# exp31ac.net
KiCad netlist of a schematic drawn in EAGLE
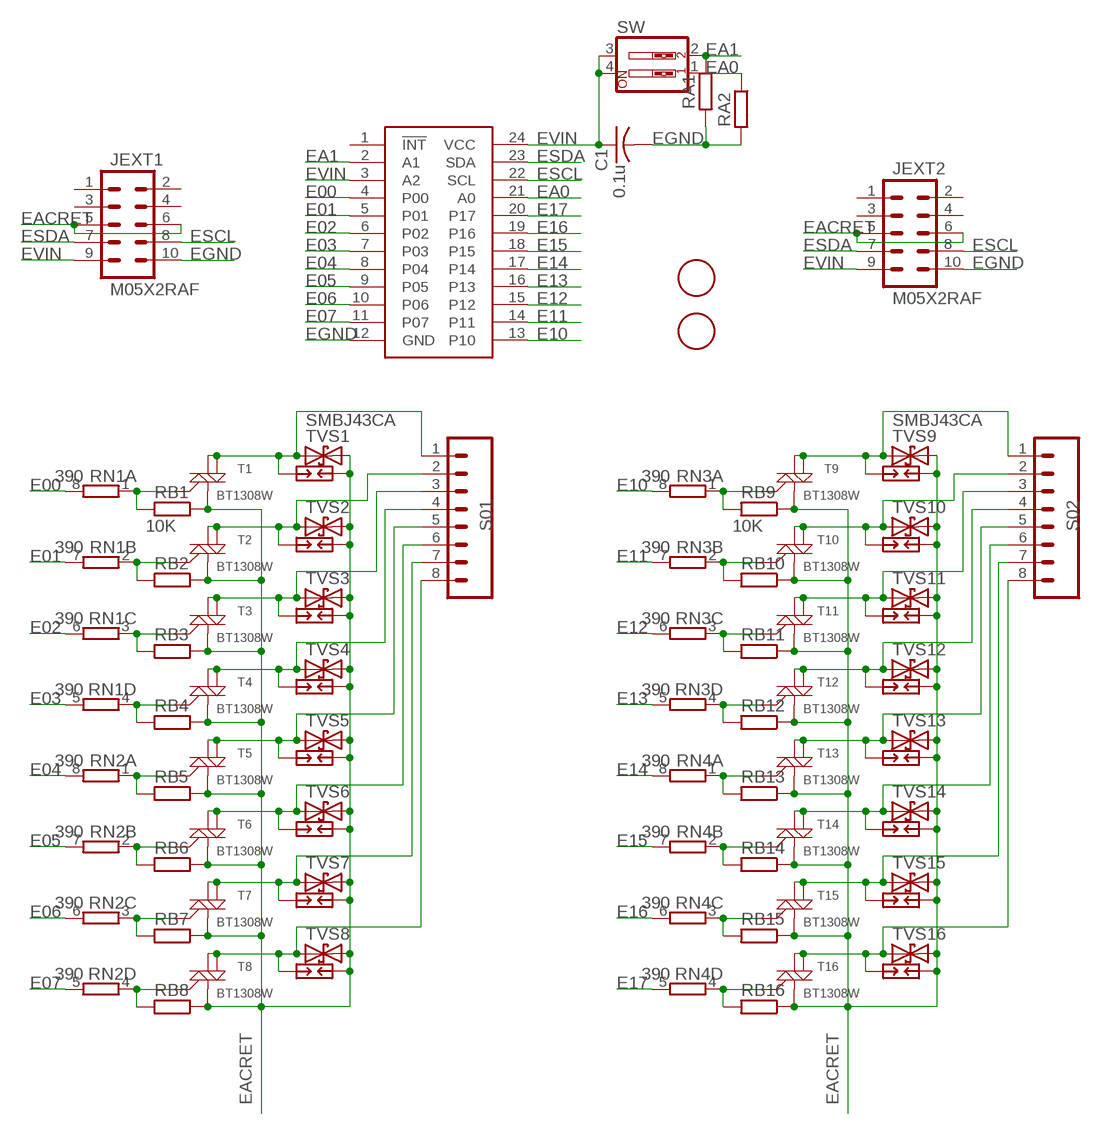
[diagram p0: schematic, sheet 1]

(export (version "E")
  (design (tool "Eeschema 10.0.6"))
  (components
    (comp (ref "C1")
      (value "0.1u")
      (footprint "eagle-import:C0603")
      (libsource (lib "eagle-import") (part "C-USC0603"))
    )
    (comp (ref "JEXT1")
      (value "M05X2RAF")
      (footprint "eagle-import:2X5-RAF")
      (libsource (lib "eagle-import") (part "M05X2RAF"))
    )
    (comp (ref "JEXT2")
      (value "M05X2RAF")
      (footprint "eagle-import:2X5-RAF")
      (libsource (lib "eagle-import") (part "M05X2RAF"))
    )
    (comp (ref "PCA9555")
      (value "PCA9555PW")
      (footprint "eagle-import:TSSOP24")
      (libsource (lib "eagle-import") (part "PCF8575TSSOP24"))
    )
    (comp (ref "RA1")
      (value "10K")
      (footprint "eagle-import:R0603")
      (libsource (lib "eagle-import") (part "R-EU_R0603"))
    )
    (comp (ref "RA2")
      (value "10K")
      (footprint "eagle-import:R0603")
      (libsource (lib "eagle-import") (part "R-EU_R0603"))
    )
    (comp (ref "RB1")
      (value "10K")
      (footprint "eagle-import:R0603")
      (libsource (lib "eagle-import") (part "R-EU_R0603"))
    )
    (comp (ref "RB2")
      (value "10K")
      (footprint "eagle-import:R0603")
      (libsource (lib "eagle-import") (part "R-EU_R0603"))
    )
    (comp (ref "RB3")
      (value "10K")
      (footprint "eagle-import:R0603")
      (libsource (lib "eagle-import") (part "R-EU_R0603"))
    )
    (comp (ref "RB4")
      (value "10K")
      (footprint "eagle-import:R0603")
      (libsource (lib "eagle-import") (part "R-EU_R0603"))
    )
    (comp (ref "RB5")
      (value "10K")
      (footprint "eagle-import:R0603")
      (libsource (lib "eagle-import") (part "R-EU_R0603"))
    )
    (comp (ref "RB6")
      (value "10K")
      (footprint "eagle-import:R0603")
      (libsource (lib "eagle-import") (part "R-EU_R0603"))
    )
    (comp (ref "RB7")
      (value "10K")
      (footprint "eagle-import:R0603")
      (libsource (lib "eagle-import") (part "R-EU_R0603"))
    )
    (comp (ref "RB8")
      (value "10K")
      (footprint "eagle-import:R0603")
      (libsource (lib "eagle-import") (part "R-EU_R0603"))
    )
    (comp (ref "RB9")
      (value "10K")
      (footprint "eagle-import:R0603")
      (libsource (lib "eagle-import") (part "R-EU_R0603"))
    )
    (comp (ref "RB10")
      (value "10K")
      (footprint "eagle-import:R0603")
      (libsource (lib "eagle-import") (part "R-EU_R0603"))
    )
    (comp (ref "RB11")
      (value "10K")
      (footprint "eagle-import:R0603")
      (libsource (lib "eagle-import") (part "R-EU_R0603"))
    )
    (comp (ref "RB12")
      (value "10K")
      (footprint "eagle-import:R0603")
      (libsource (lib "eagle-import") (part "R-EU_R0603"))
    )
    (comp (ref "RB13")
      (value "10K")
      (footprint "eagle-import:R0603")
      (libsource (lib "eagle-import") (part "R-EU_R0603"))
    )
    (comp (ref "RB14")
      (value "10K")
      (footprint "eagle-import:R0603")
      (libsource (lib "eagle-import") (part "R-EU_R0603"))
    )
    (comp (ref "RB15")
      (value "10K")
      (footprint "eagle-import:R0603")
      (libsource (lib "eagle-import") (part "R-EU_R0603"))
    )
    (comp (ref "RB16")
      (value "10K")
      (footprint "eagle-import:R0603")
      (libsource (lib "eagle-import") (part "R-EU_R0603"))
    )
    (comp (ref "RN1")
      (value "390")
      (footprint "eagle-import:EXB38V")
      (libsource (lib "eagle-import") (part "4R-NEXB38V"))
    )
    (comp (ref "RN2")
      (value "390")
      (footprint "eagle-import:EXB38V")
      (libsource (lib "eagle-import") (part "4R-NEXB38V"))
    )
    (comp (ref "RN3")
      (value "390")
      (footprint "eagle-import:EXB38V")
      (libsource (lib "eagle-import") (part "4R-NEXB38V"))
    )
    (comp (ref "RN4")
      (value "390")
      (footprint "eagle-import:EXB38V")
      (libsource (lib "eagle-import") (part "4R-NEXB38V"))
    )
    (comp (ref "S01")
      (value "M085MM-8")
      (footprint "eagle-import:SCREWTERMINAL-5MM-8")
      (libsource (lib "eagle-import") (part "M085MM-8"))
    )
    (comp (ref "S02")
      (value "M085MM-8")
      (footprint "eagle-import:SCREWTERMINAL-5MM-8")
      (libsource (lib "eagle-import") (part "M085MM-8"))
    )
    (comp (ref "SP1")
      (value "PCB-SGAP")
      (footprint "eagle-import:PCB-SGAP")
      (libsource (lib "eagle-import") (part "PCB-SGAP"))
    )
    (comp (ref "SP2")
      (value "PCB-SGAP")
      (footprint "eagle-import:PCB-SGAP")
      (libsource (lib "eagle-import") (part "PCB-SGAP"))
    )
    (comp (ref "SP3")
      (value "PCB-SGAP")
      (footprint "eagle-import:PCB-SGAP")
      (libsource (lib "eagle-import") (part "PCB-SGAP"))
    )
    (comp (ref "SP4")
      (value "PCB-SGAP")
      (footprint "eagle-import:PCB-SGAP")
      (libsource (lib "eagle-import") (part "PCB-SGAP"))
    )
    (comp (ref "SP5")
      (value "PCB-SGAP")
      (footprint "eagle-import:PCB-SGAP")
      (libsource (lib "eagle-import") (part "PCB-SGAP"))
    )
    (comp (ref "SP6")
      (value "PCB-SGAP")
      (footprint "eagle-import:PCB-SGAP")
      (libsource (lib "eagle-import") (part "PCB-SGAP"))
    )
    (comp (ref "SP7")
      (value "PCB-SGAP")
      (footprint "eagle-import:PCB-SGAP")
      (libsource (lib "eagle-import") (part "PCB-SGAP"))
    )
    (comp (ref "SP8")
      (value "PCB-SGAP")
      (footprint "eagle-import:PCB-SGAP")
      (libsource (lib "eagle-import") (part "PCB-SGAP"))
    )
    (comp (ref "SP9")
      (value "PCB-SGAP")
      (footprint "eagle-import:PCB-SGAP")
      (libsource (lib "eagle-import") (part "PCB-SGAP"))
    )
    (comp (ref "SP10")
      (value "PCB-SGAP")
      (footprint "eagle-import:PCB-SGAP")
      (libsource (lib "eagle-import") (part "PCB-SGAP"))
    )
    (comp (ref "SP11")
      (value "PCB-SGAP")
      (footprint "eagle-import:PCB-SGAP")
      (libsource (lib "eagle-import") (part "PCB-SGAP"))
    )
    (comp (ref "SP12")
      (value "PCB-SGAP")
      (footprint "eagle-import:PCB-SGAP")
      (libsource (lib "eagle-import") (part "PCB-SGAP"))
    )
    (comp (ref "SP13")
      (value "PCB-SGAP")
      (footprint "eagle-import:PCB-SGAP")
      (libsource (lib "eagle-import") (part "PCB-SGAP"))
    )
    (comp (ref "SP14")
      (value "PCB-SGAP")
      (footprint "eagle-import:PCB-SGAP")
      (libsource (lib "eagle-import") (part "PCB-SGAP"))
    )
    (comp (ref "SP15")
      (value "PCB-SGAP")
      (footprint "eagle-import:PCB-SGAP")
      (libsource (lib "eagle-import") (part "PCB-SGAP"))
    )
    (comp (ref "SP16")
      (value "PCB-SGAP")
      (footprint "eagle-import:PCB-SGAP")
      (libsource (lib "eagle-import") (part "PCB-SGAP"))
    )
    (comp (ref "SW")
      (value "SW_DIP-2")
      (footprint "eagle-import:DIPSWITCH-02")
      (libsource (lib "eagle-import") (part "SW_DIP-2"))
    )
    (comp (ref "T1")
      (value "BT1308W")
      (footprint "eagle-import:SOT223")
      (libsource (lib "eagle-import") (part "MAC97SOT223"))
    )
    (comp (ref "T2")
      (value "BT1308W")
      (footprint "eagle-import:SOT223")
      (libsource (lib "eagle-import") (part "MAC97SOT223"))
    )
    (comp (ref "T3")
      (value "BT1308W")
      (footprint "eagle-import:SOT223")
      (libsource (lib "eagle-import") (part "MAC97SOT223"))
    )
    (comp (ref "T4")
      (value "BT1308W")
      (footprint "eagle-import:SOT223")
      (libsource (lib "eagle-import") (part "MAC97SOT223"))
    )
    (comp (ref "T5")
      (value "BT1308W")
      (footprint "eagle-import:SOT223")
      (libsource (lib "eagle-import") (part "MAC97SOT223"))
    )
    (comp (ref "T6")
      (value "BT1308W")
      (footprint "eagle-import:SOT223")
      (libsource (lib "eagle-import") (part "MAC97SOT223"))
    )
    (comp (ref "T7")
      (value "BT1308W")
      (footprint "eagle-import:SOT223")
      (libsource (lib "eagle-import") (part "MAC97SOT223"))
    )
    (comp (ref "T8")
      (value "BT1308W")
      (footprint "eagle-import:SOT223")
      (libsource (lib "eagle-import") (part "MAC97SOT223"))
    )
    (comp (ref "T9")
      (value "BT1308W")
      (footprint "eagle-import:SOT223")
      (libsource (lib "eagle-import") (part "MAC97SOT223"))
    )
    (comp (ref "T10")
      (value "BT1308W")
      (footprint "eagle-import:SOT223")
      (libsource (lib "eagle-import") (part "MAC97SOT223"))
    )
    (comp (ref "T11")
      (value "BT1308W")
      (footprint "eagle-import:SOT223")
      (libsource (lib "eagle-import") (part "MAC97SOT223"))
    )
    (comp (ref "T12")
      (value "BT1308W")
      (footprint "eagle-import:SOT223")
      (libsource (lib "eagle-import") (part "MAC97SOT223"))
    )
    (comp (ref "T13")
      (value "BT1308W")
      (footprint "eagle-import:SOT223")
      (libsource (lib "eagle-import") (part "MAC97SOT223"))
    )
    (comp (ref "T14")
      (value "BT1308W")
      (footprint "eagle-import:SOT223")
      (libsource (lib "eagle-import") (part "MAC97SOT223"))
    )
    (comp (ref "T15")
      (value "BT1308W")
      (footprint "eagle-import:SOT223")
      (libsource (lib "eagle-import") (part "MAC97SOT223"))
    )
    (comp (ref "T16")
      (value "BT1308W")
      (footprint "eagle-import:SOT223")
      (libsource (lib "eagle-import") (part "MAC97SOT223"))
    )
    (comp (ref "TVS1")
      (value "SMBJ43CA")
      (footprint "eagle-import:SMB")
      (libsource (lib "eagle-import") (part "TVSSMB"))
    )
    (comp (ref "TVS2")
      (value "SMBJ43CA")
      (footprint "eagle-import:SMB")
      (libsource (lib "eagle-import") (part "TVSSMB"))
    )
    (comp (ref "TVS3")
      (value "SMBJ43CA")
      (footprint "eagle-import:SMB")
      (libsource (lib "eagle-import") (part "TVSSMB"))
    )
    (comp (ref "TVS4")
      (value "SMBJ43CA")
      (footprint "eagle-import:SMB")
      (libsource (lib "eagle-import") (part "TVSSMB"))
    )
    (comp (ref "TVS5")
      (value "SMBJ43CA")
      (footprint "eagle-import:SMB")
      (libsource (lib "eagle-import") (part "TVSSMB"))
    )
    (comp (ref "TVS6")
      (value "SMBJ43CA")
      (footprint "eagle-import:SMB")
      (libsource (lib "eagle-import") (part "TVSSMB"))
    )
    (comp (ref "TVS7")
      (value "SMBJ43CA")
      (footprint "eagle-import:SMB")
      (libsource (lib "eagle-import") (part "TVSSMB"))
    )
    (comp (ref "TVS8")
      (value "SMBJ43CA")
      (footprint "eagle-import:SMB")
      (libsource (lib "eagle-import") (part "TVSSMB"))
    )
    (comp (ref "TVS9")
      (value "SMBJ43CA")
      (footprint "eagle-import:SMB")
      (libsource (lib "eagle-import") (part "TVSSMB"))
    )
    (comp (ref "TVS10")
      (value "SMBJ43CA")
      (footprint "eagle-import:SMB")
      (libsource (lib "eagle-import") (part "TVSSMB"))
    )
    (comp (ref "TVS11")
      (value "SMBJ43CA")
      (footprint "eagle-import:SMB")
      (libsource (lib "eagle-import") (part "TVSSMB"))
    )
    (comp (ref "TVS12")
      (value "SMBJ43CA")
      (footprint "eagle-import:SMB")
      (libsource (lib "eagle-import") (part "TVSSMB"))
    )
    (comp (ref "TVS13")
      (value "SMBJ43CA")
      (footprint "eagle-import:SMB")
      (libsource (lib "eagle-import") (part "TVSSMB"))
    )
    (comp (ref "TVS14")
      (value "SMBJ43CA")
      (footprint "eagle-import:SMB")
      (libsource (lib "eagle-import") (part "TVSSMB"))
    )
    (comp (ref "TVS15")
      (value "SMBJ43CA")
      (footprint "eagle-import:SMB")
      (libsource (lib "eagle-import") (part "TVSSMB"))
    )
    (comp (ref "TVS16")
      (value "SMBJ43CA")
      (footprint "eagle-import:SMB")
      (libsource (lib "eagle-import") (part "TVSSMB"))
    )
    (comp (ref "U$1")
      (value "FIDUCIAL")
      (footprint "eagle-import:FIDUCIAL_1MM")
      (libsource (lib "eagle-import") (part "FIDUCIAL"))
    )
    (comp (ref "U$2")
      (value "FIDUCIAL")
      (footprint "eagle-import:FIDUCIAL_1MM")
      (libsource (lib "eagle-import") (part "FIDUCIAL"))
    )
  )
  (nets
    (net (code "1") (name "/E00") (class "Default")
      (node (ref "PCA9555") (pin "4") (pinfunction "P00_4") (pintype "bidirectional"))
      (node (ref "RN1") (pin "8") (pinfunction "2_8") (pintype "passive"))
    )
    (net (code "2") (name "/E01") (class "Default")
      (node (ref "PCA9555") (pin "5") (pinfunction "P01_5") (pintype "bidirectional"))
      (node (ref "RN1") (pin "7") (pinfunction "2_7") (pintype "passive"))
    )
    (net (code "3") (name "/E02") (class "Default")
      (node (ref "PCA9555") (pin "6") (pinfunction "P02_6") (pintype "bidirectional"))
      (node (ref "RN1") (pin "6") (pinfunction "2_6") (pintype "passive"))
    )
    (net (code "4") (name "/E03") (class "Default")
      (node (ref "PCA9555") (pin "7") (pinfunction "P03_7") (pintype "bidirectional"))
      (node (ref "RN1") (pin "5") (pinfunction "2_5") (pintype "passive"))
    )
    (net (code "5") (name "/E04") (class "Default")
      (node (ref "PCA9555") (pin "8") (pinfunction "P04_8") (pintype "bidirectional"))
      (node (ref "RN2") (pin "8") (pinfunction "2_8") (pintype "passive"))
    )
    (net (code "6") (name "/E05") (class "Default")
      (node (ref "PCA9555") (pin "9") (pinfunction "P05_9") (pintype "bidirectional"))
      (node (ref "RN2") (pin "7") (pinfunction "2_7") (pintype "passive"))
    )
    (net (code "7") (name "/E06") (class "Default")
      (node (ref "PCA9555") (pin "10") (pinfunction "P06_10") (pintype "bidirectional"))
      (node (ref "RN2") (pin "6") (pinfunction "2_6") (pintype "passive"))
    )
    (net (code "8") (name "/E07") (class "Default")
      (node (ref "PCA9555") (pin "11") (pinfunction "P07_11") (pintype "bidirectional"))
      (node (ref "RN2") (pin "5") (pinfunction "2_5") (pintype "passive"))
    )
    (net (code "9") (name "/E10") (class "Default")
      (node (ref "PCA9555") (pin "13") (pinfunction "P10_13") (pintype "bidirectional"))
      (node (ref "RN3") (pin "8") (pinfunction "2_8") (pintype "passive"))
    )
    (net (code "10") (name "/E11") (class "Default")
      (node (ref "PCA9555") (pin "14") (pinfunction "P11_14") (pintype "bidirectional"))
      (node (ref "RN3") (pin "7") (pinfunction "2_7") (pintype "passive"))
    )
    (net (code "11") (name "/E12") (class "Default")
      (node (ref "PCA9555") (pin "15") (pinfunction "P12_15") (pintype "bidirectional"))
      (node (ref "RN3") (pin "6") (pinfunction "2_6") (pintype "passive"))
    )
    (net (code "12") (name "/E13") (class "Default")
      (node (ref "PCA9555") (pin "16") (pinfunction "P13_16") (pintype "bidirectional"))
      (node (ref "RN3") (pin "5") (pinfunction "2_5") (pintype "passive"))
    )
    (net (code "13") (name "/E14") (class "Default")
      (node (ref "PCA9555") (pin "17") (pinfunction "P14_17") (pintype "bidirectional"))
      (node (ref "RN4") (pin "8") (pinfunction "2_8") (pintype "passive"))
    )
    (net (code "14") (name "/E15") (class "Default")
      (node (ref "PCA9555") (pin "18") (pinfunction "P15_18") (pintype "bidirectional"))
      (node (ref "RN4") (pin "7") (pinfunction "2_7") (pintype "passive"))
    )
    (net (code "15") (name "/E16") (class "Default")
      (node (ref "PCA9555") (pin "19") (pinfunction "P16_19") (pintype "bidirectional"))
      (node (ref "RN4") (pin "6") (pinfunction "2_6") (pintype "passive"))
    )
    (net (code "16") (name "/E17") (class "Default")
      (node (ref "PCA9555") (pin "20") (pinfunction "P17_20") (pintype "bidirectional"))
      (node (ref "RN4") (pin "5") (pinfunction "2_5") (pintype "passive"))
    )
    (net (code "17") (name "/EA0") (class "Default")
      (node (ref "PCA9555") (pin "21") (pinfunction "A0_21") (pintype "bidirectional"))
      (node (ref "RA2") (pin "1") (pinfunction "1_1") (pintype "passive"))
      (node (ref "SW") (pin "1") (pinfunction "1_1") (pintype "passive"))
    )
    (net (code "18") (name "/EA1") (class "Default")
      (node (ref "PCA9555") (pin "2") (pinfunction "A1_2") (pintype "bidirectional"))
      (node (ref "RA1") (pin "1") (pinfunction "1_1") (pintype "passive"))
      (node (ref "SW") (pin "2") (pinfunction "2_2") (pintype "passive"))
    )
    (net (code "19") (name "/EACRET") (class "Default")
      (node (ref "JEXT1") (pin "5") (pinfunction "5_5") (pintype "passive"))
      (node (ref "JEXT1") (pin "6") (pinfunction "6_6") (pintype "passive"))
      (node (ref "JEXT2") (pin "5") (pinfunction "5_5") (pintype "passive"))
      (node (ref "JEXT2") (pin "6") (pinfunction "6_6") (pintype "passive"))
      (node (ref "RB1") (pin "1") (pinfunction "1_1") (pintype "passive"))
      (node (ref "RB10") (pin "1") (pinfunction "1_1") (pintype "passive"))
      (node (ref "RB11") (pin "1") (pinfunction "1_1") (pintype "passive"))
      (node (ref "RB12") (pin "1") (pinfunction "1_1") (pintype "passive"))
      (node (ref "RB13") (pin "1") (pinfunction "1_1") (pintype "passive"))
      (node (ref "RB14") (pin "1") (pinfunction "1_1") (pintype "passive"))
      (node (ref "RB15") (pin "1") (pinfunction "1_1") (pintype "passive"))
      (node (ref "RB16") (pin "1") (pinfunction "1_1") (pintype "passive"))
      (node (ref "RB2") (pin "1") (pinfunction "1_1") (pintype "passive"))
      (node (ref "RB3") (pin "1") (pinfunction "1_1") (pintype "passive"))
      (node (ref "RB4") (pin "1") (pinfunction "1_1") (pintype "passive"))
      (node (ref "RB5") (pin "1") (pinfunction "1_1") (pintype "passive"))
      (node (ref "RB6") (pin "1") (pinfunction "1_1") (pintype "passive"))
      (node (ref "RB7") (pin "1") (pinfunction "1_1") (pintype "passive"))
      (node (ref "RB8") (pin "1") (pinfunction "1_1") (pintype "passive"))
      (node (ref "RB9") (pin "1") (pinfunction "1_1") (pintype "passive"))
      (node (ref "SP1") (pin "1") (pinfunction "1_1") (pintype "passive"))
      (node (ref "SP10") (pin "1") (pinfunction "1_1") (pintype "passive"))
      (node (ref "SP11") (pin "1") (pinfunction "1_1") (pintype "passive"))
      (node (ref "SP12") (pin "1") (pinfunction "1_1") (pintype "passive"))
      (node (ref "SP13") (pin "1") (pinfunction "1_1") (pintype "passive"))
      (node (ref "SP14") (pin "1") (pinfunction "1_1") (pintype "passive"))
      (node (ref "SP15") (pin "1") (pinfunction "1_1") (pintype "passive"))
      (node (ref "SP16") (pin "1") (pinfunction "1_1") (pintype "passive"))
      (node (ref "SP2") (pin "1") (pinfunction "1_1") (pintype "passive"))
      (node (ref "SP3") (pin "1") (pinfunction "1_1") (pintype "passive"))
      (node (ref "SP4") (pin "1") (pinfunction "1_1") (pintype "passive"))
      (node (ref "SP5") (pin "1") (pinfunction "1_1") (pintype "passive"))
      (node (ref "SP6") (pin "1") (pinfunction "1_1") (pintype "passive"))
      (node (ref "SP7") (pin "1") (pinfunction "1_1") (pintype "passive"))
      (node (ref "SP8") (pin "1") (pinfunction "1_1") (pintype "passive"))
      (node (ref "SP9") (pin "1") (pinfunction "1_1") (pintype "passive"))
      (node (ref "T1") (pin "1") (pinfunction "M1_1") (pintype "bidirectional"))
      (node (ref "T10") (pin "1") (pinfunction "M1_1") (pintype "bidirectional"))
      (node (ref "T11") (pin "1") (pinfunction "M1_1") (pintype "bidirectional"))
      (node (ref "T12") (pin "1") (pinfunction "M1_1") (pintype "bidirectional"))
      (node (ref "T13") (pin "1") (pinfunction "M1_1") (pintype "bidirectional"))
      (node (ref "T14") (pin "1") (pinfunction "M1_1") (pintype "bidirectional"))
      (node (ref "T15") (pin "1") (pinfunction "M1_1") (pintype "bidirectional"))
      (node (ref "T16") (pin "1") (pinfunction "M1_1") (pintype "bidirectional"))
      (node (ref "T2") (pin "1") (pinfunction "M1_1") (pintype "bidirectional"))
      (node (ref "T3") (pin "1") (pinfunction "M1_1") (pintype "bidirectional"))
      (node (ref "T4") (pin "1") (pinfunction "M1_1") (pintype "bidirectional"))
      (node (ref "T5") (pin "1") (pinfunction "M1_1") (pintype "bidirectional"))
      (node (ref "T6") (pin "1") (pinfunction "M1_1") (pintype "bidirectional"))
      (node (ref "T7") (pin "1") (pinfunction "M1_1") (pintype "bidirectional"))
      (node (ref "T8") (pin "1") (pinfunction "M1_1") (pintype "bidirectional"))
      (node (ref "T9") (pin "1") (pinfunction "M1_1") (pintype "bidirectional"))
      (node (ref "TVS1") (pin "C") (pinfunction "C_C") (pintype "passive"))
      (node (ref "TVS10") (pin "C") (pinfunction "C_C") (pintype "passive"))
      (node (ref "TVS11") (pin "C") (pinfunction "C_C") (pintype "passive"))
      (node (ref "TVS12") (pin "C") (pinfunction "C_C") (pintype "passive"))
      (node (ref "TVS13") (pin "C") (pinfunction "C_C") (pintype "passive"))
      (node (ref "TVS14") (pin "C") (pinfunction "C_C") (pintype "passive"))
      (node (ref "TVS15") (pin "C") (pinfunction "C_C") (pintype "passive"))
      (node (ref "TVS16") (pin "C") (pinfunction "C_C") (pintype "passive"))
      (node (ref "TVS2") (pin "C") (pinfunction "C_C") (pintype "passive"))
      (node (ref "TVS3") (pin "C") (pinfunction "C_C") (pintype "passive"))
      (node (ref "TVS4") (pin "C") (pinfunction "C_C") (pintype "passive"))
      (node (ref "TVS5") (pin "C") (pinfunction "C_C") (pintype "passive"))
      (node (ref "TVS6") (pin "C") (pinfunction "C_C") (pintype "passive"))
      (node (ref "TVS7") (pin "C") (pinfunction "C_C") (pintype "passive"))
      (node (ref "TVS8") (pin "C") (pinfunction "C_C") (pintype "passive"))
      (node (ref "TVS9") (pin "C") (pinfunction "C_C") (pintype "passive"))
    )
    (net (code "20") (name "/EGND") (class "Default")
      (node (ref "C1") (pin "2") (pinfunction "2_2") (pintype "passive"))
      (node (ref "JEXT1") (pin "10") (pinfunction "10_10") (pintype "passive"))
      (node (ref "JEXT2") (pin "10") (pinfunction "10_10") (pintype "passive"))
      (node (ref "PCA9555") (pin "12") (pinfunction "GND_12") (pintype "power_in"))
      (node (ref "RA1") (pin "2") (pinfunction "2_2") (pintype "passive"))
      (node (ref "RA2") (pin "2") (pinfunction "2_2") (pintype "passive"))
    )
    (net (code "21") (name "/ESCL") (class "Default")
      (node (ref "JEXT1") (pin "8") (pinfunction "8_8") (pintype "passive"))
      (node (ref "JEXT2") (pin "8") (pinfunction "8_8") (pintype "passive"))
      (node (ref "PCA9555") (pin "22") (pinfunction "SCL_22") (pintype "bidirectional"))
    )
    (net (code "22") (name "/ESDA") (class "Default")
      (node (ref "JEXT1") (pin "7") (pinfunction "7_7") (pintype "passive"))
      (node (ref "JEXT2") (pin "7") (pinfunction "7_7") (pintype "passive"))
      (node (ref "PCA9555") (pin "23") (pinfunction "SDA_23") (pintype "bidirectional"))
    )
    (net (code "23") (name "/EVIN") (class "Default")
      (node (ref "C1") (pin "1") (pinfunction "1_1") (pintype "passive"))
      (node (ref "JEXT1") (pin "9") (pinfunction "9_9") (pintype "passive"))
      (node (ref "JEXT2") (pin "9") (pinfunction "9_9") (pintype "passive"))
      (node (ref "PCA9555") (pin "24") (pinfunction "VCC_24") (pintype "power_in"))
      (node (ref "PCA9555") (pin "3") (pinfunction "A2_3") (pintype "bidirectional"))
      (node (ref "SW") (pin "3") (pinfunction "3_3") (pintype "passive"))
      (node (ref "SW") (pin "4") (pinfunction "4_4") (pintype "passive"))
    )
    (net (code "24") (name "Net-(RN1B-1)") (class "Default")
      (node (ref "RB2") (pin "2") (pinfunction "2_2") (pintype "passive"))
      (node (ref "RN1") (pin "2") (pinfunction "1_2") (pintype "passive"))
      (node (ref "T2") (pin "3") (pinfunction "G_3") (pintype "bidirectional"))
    )
    (net (code "25") (name "Net-(RN1C-1)") (class "Default")
      (node (ref "RB3") (pin "2") (pinfunction "2_2") (pintype "passive"))
      (node (ref "RN1") (pin "3") (pinfunction "1_3") (pintype "passive"))
      (node (ref "T3") (pin "3") (pinfunction "G_3") (pintype "bidirectional"))
    )
    (net (code "26") (name "Net-(RN1D-1)") (class "Default")
      (node (ref "RB4") (pin "2") (pinfunction "2_2") (pintype "passive"))
      (node (ref "RN1") (pin "4") (pinfunction "1_4") (pintype "passive"))
      (node (ref "T4") (pin "3") (pinfunction "G_3") (pintype "bidirectional"))
    )
    (net (code "27") (name "Net-(RN2B-1)") (class "Default")
      (node (ref "RB6") (pin "2") (pinfunction "2_2") (pintype "passive"))
      (node (ref "RN2") (pin "2") (pinfunction "1_2") (pintype "passive"))
      (node (ref "T6") (pin "3") (pinfunction "G_3") (pintype "bidirectional"))
    )
    (net (code "28") (name "Net-(RN2C-1)") (class "Default")
      (node (ref "RB7") (pin "2") (pinfunction "2_2") (pintype "passive"))
      (node (ref "RN2") (pin "3") (pinfunction "1_3") (pintype "passive"))
      (node (ref "T7") (pin "3") (pinfunction "G_3") (pintype "bidirectional"))
    )
    (net (code "29") (name "Net-(RN2D-1)") (class "Default")
      (node (ref "RB8") (pin "2") (pinfunction "2_2") (pintype "passive"))
      (node (ref "RN2") (pin "4") (pinfunction "1_4") (pintype "passive"))
      (node (ref "T8") (pin "3") (pinfunction "G_3") (pintype "bidirectional"))
    )
    (net (code "30") (name "Net-(RN3B-1)") (class "Default")
      (node (ref "RB10") (pin "2") (pinfunction "2_2") (pintype "passive"))
      (node (ref "RN3") (pin "2") (pinfunction "1_2") (pintype "passive"))
      (node (ref "T10") (pin "3") (pinfunction "G_3") (pintype "bidirectional"))
    )
    (net (code "31") (name "Net-(RN3C-1)") (class "Default")
      (node (ref "RB11") (pin "2") (pinfunction "2_2") (pintype "passive"))
      (node (ref "RN3") (pin "3") (pinfunction "1_3") (pintype "passive"))
      (node (ref "T11") (pin "3") (pinfunction "G_3") (pintype "bidirectional"))
    )
    (net (code "32") (name "Net-(RN3D-1)") (class "Default")
      (node (ref "RB12") (pin "2") (pinfunction "2_2") (pintype "passive"))
      (node (ref "RN3") (pin "4") (pinfunction "1_4") (pintype "passive"))
      (node (ref "T12") (pin "3") (pinfunction "G_3") (pintype "bidirectional"))
    )
    (net (code "33") (name "Net-(RN4B-1)") (class "Default")
      (node (ref "RB14") (pin "2") (pinfunction "2_2") (pintype "passive"))
      (node (ref "RN4") (pin "2") (pinfunction "1_2") (pintype "passive"))
      (node (ref "T14") (pin "3") (pinfunction "G_3") (pintype "bidirectional"))
    )
    (net (code "34") (name "Net-(RN4C-1)") (class "Default")
      (node (ref "RB15") (pin "2") (pinfunction "2_2") (pintype "passive"))
      (node (ref "RN4") (pin "3") (pinfunction "1_3") (pintype "passive"))
      (node (ref "T15") (pin "3") (pinfunction "G_3") (pintype "bidirectional"))
    )
    (net (code "35") (name "Net-(RN4D-1)") (class "Default")
      (node (ref "RB16") (pin "2") (pinfunction "2_2") (pintype "passive"))
      (node (ref "RN4") (pin "4") (pinfunction "1_4") (pintype "passive"))
      (node (ref "T16") (pin "3") (pinfunction "G_3") (pintype "bidirectional"))
    )
    (net (code "36") (name "Net-(T1-G)") (class "Default")
      (node (ref "RB1") (pin "2") (pinfunction "2_2") (pintype "passive"))
      (node (ref "RN1") (pin "1") (pinfunction "1_1") (pintype "passive"))
      (node (ref "T1") (pin "3") (pinfunction "G_3") (pintype "bidirectional"))
    )
    (net (code "37") (name "Net-(T1-M2)") (class "Default")
      (node (ref "S01") (pin "1") (pinfunction "1_1") (pintype "passive"))
      (node (ref "SP1") (pin "2") (pinfunction "2_2") (pintype "passive"))
      (node (ref "T1") (pin "2") (pinfunction "M2_2") (pintype "bidirectional"))
      (node (ref "T1") (pin "4") (pinfunction "M2-4_4") (pintype "bidirectional"))
      (node (ref "TVS1") (pin "A") (pinfunction "A_A") (pintype "passive"))
    )
    (net (code "38") (name "Net-(T2-M2)") (class "Default")
      (node (ref "S01") (pin "2") (pinfunction "2_2") (pintype "passive"))
      (node (ref "SP2") (pin "2") (pinfunction "2_2") (pintype "passive"))
      (node (ref "T2") (pin "2") (pinfunction "M2_2") (pintype "bidirectional"))
      (node (ref "T2") (pin "4") (pinfunction "M2-4_4") (pintype "bidirectional"))
      (node (ref "TVS2") (pin "A") (pinfunction "A_A") (pintype "passive"))
    )
    (net (code "39") (name "Net-(T3-M2)") (class "Default")
      (node (ref "S01") (pin "3") (pinfunction "3_3") (pintype "passive"))
      (node (ref "SP3") (pin "2") (pinfunction "2_2") (pintype "passive"))
      (node (ref "T3") (pin "2") (pinfunction "M2_2") (pintype "bidirectional"))
      (node (ref "T3") (pin "4") (pinfunction "M2-4_4") (pintype "bidirectional"))
      (node (ref "TVS3") (pin "A") (pinfunction "A_A") (pintype "passive"))
    )
    (net (code "40") (name "Net-(T4-M2)") (class "Default")
      (node (ref "S01") (pin "4") (pinfunction "4_4") (pintype "passive"))
      (node (ref "SP4") (pin "2") (pinfunction "2_2") (pintype "passive"))
      (node (ref "T4") (pin "2") (pinfunction "M2_2") (pintype "bidirectional"))
      (node (ref "T4") (pin "4") (pinfunction "M2-4_4") (pintype "bidirectional"))
      (node (ref "TVS4") (pin "A") (pinfunction "A_A") (pintype "passive"))
    )
    (net (code "41") (name "Net-(T5-G)") (class "Default")
      (node (ref "RB5") (pin "2") (pinfunction "2_2") (pintype "passive"))
      (node (ref "RN2") (pin "1") (pinfunction "1_1") (pintype "passive"))
      (node (ref "T5") (pin "3") (pinfunction "G_3") (pintype "bidirectional"))
    )
    (net (code "42") (name "Net-(T5-M2)") (class "Default")
      (node (ref "S01") (pin "5") (pinfunction "5_5") (pintype "passive"))
      (node (ref "SP5") (pin "2") (pinfunction "2_2") (pintype "passive"))
      (node (ref "T5") (pin "2") (pinfunction "M2_2") (pintype "bidirectional"))
      (node (ref "T5") (pin "4") (pinfunction "M2-4_4") (pintype "bidirectional"))
      (node (ref "TVS5") (pin "A") (pinfunction "A_A") (pintype "passive"))
    )
    (net (code "43") (name "Net-(T6-M2)") (class "Default")
      (node (ref "S01") (pin "6") (pinfunction "6_6") (pintype "passive"))
      (node (ref "SP6") (pin "2") (pinfunction "2_2") (pintype "passive"))
      (node (ref "T6") (pin "2") (pinfunction "M2_2") (pintype "bidirectional"))
      (node (ref "T6") (pin "4") (pinfunction "M2-4_4") (pintype "bidirectional"))
      (node (ref "TVS6") (pin "A") (pinfunction "A_A") (pintype "passive"))
    )
    (net (code "44") (name "Net-(T7-M2)") (class "Default")
      (node (ref "S01") (pin "7") (pinfunction "7_7") (pintype "passive"))
      (node (ref "SP7") (pin "2") (pinfunction "2_2") (pintype "passive"))
      (node (ref "T7") (pin "2") (pinfunction "M2_2") (pintype "bidirectional"))
      (node (ref "T7") (pin "4") (pinfunction "M2-4_4") (pintype "bidirectional"))
      (node (ref "TVS7") (pin "A") (pinfunction "A_A") (pintype "passive"))
    )
    (net (code "45") (name "Net-(T8-M2)") (class "Default")
      (node (ref "S01") (pin "8") (pinfunction "8_8") (pintype "passive"))
      (node (ref "SP8") (pin "2") (pinfunction "2_2") (pintype "passive"))
      (node (ref "T8") (pin "2") (pinfunction "M2_2") (pintype "bidirectional"))
      (node (ref "T8") (pin "4") (pinfunction "M2-4_4") (pintype "bidirectional"))
      (node (ref "TVS8") (pin "A") (pinfunction "A_A") (pintype "passive"))
    )
    (net (code "46") (name "Net-(T9-G)") (class "Default")
      (node (ref "RB9") (pin "2") (pinfunction "2_2") (pintype "passive"))
      (node (ref "RN3") (pin "1") (pinfunction "1_1") (pintype "passive"))
      (node (ref "T9") (pin "3") (pinfunction "G_3") (pintype "bidirectional"))
    )
    (net (code "47") (name "Net-(T9-M2)") (class "Default")
      (node (ref "S02") (pin "1") (pinfunction "1_1") (pintype "passive"))
      (node (ref "SP9") (pin "2") (pinfunction "2_2") (pintype "passive"))
      (node (ref "T9") (pin "2") (pinfunction "M2_2") (pintype "bidirectional"))
      (node (ref "T9") (pin "4") (pinfunction "M2-4_4") (pintype "bidirectional"))
      (node (ref "TVS9") (pin "A") (pinfunction "A_A") (pintype "passive"))
    )
    (net (code "48") (name "Net-(T10-M2)") (class "Default")
      (node (ref "S02") (pin "2") (pinfunction "2_2") (pintype "passive"))
      (node (ref "SP10") (pin "2") (pinfunction "2_2") (pintype "passive"))
      (node (ref "T10") (pin "2") (pinfunction "M2_2") (pintype "bidirectional"))
      (node (ref "T10") (pin "4") (pinfunction "M2-4_4") (pintype "bidirectional"))
      (node (ref "TVS10") (pin "A") (pinfunction "A_A") (pintype "passive"))
    )
    (net (code "49") (name "Net-(T11-M2)") (class "Default")
      (node (ref "S02") (pin "3") (pinfunction "3_3") (pintype "passive"))
      (node (ref "SP11") (pin "2") (pinfunction "2_2") (pintype "passive"))
      (node (ref "T11") (pin "2") (pinfunction "M2_2") (pintype "bidirectional"))
      (node (ref "T11") (pin "4") (pinfunction "M2-4_4") (pintype "bidirectional"))
      (node (ref "TVS11") (pin "A") (pinfunction "A_A") (pintype "passive"))
    )
    (net (code "50") (name "Net-(T12-M2)") (class "Default")
      (node (ref "S02") (pin "4") (pinfunction "4_4") (pintype "passive"))
      (node (ref "SP12") (pin "2") (pinfunction "2_2") (pintype "passive"))
      (node (ref "T12") (pin "2") (pinfunction "M2_2") (pintype "bidirectional"))
      (node (ref "T12") (pin "4") (pinfunction "M2-4_4") (pintype "bidirectional"))
      (node (ref "TVS12") (pin "A") (pinfunction "A_A") (pintype "passive"))
    )
    (net (code "51") (name "Net-(T13-G)") (class "Default")
      (node (ref "RB13") (pin "2") (pinfunction "2_2") (pintype "passive"))
      (node (ref "RN4") (pin "1") (pinfunction "1_1") (pintype "passive"))
      (node (ref "T13") (pin "3") (pinfunction "G_3") (pintype "bidirectional"))
    )
    (net (code "52") (name "Net-(T13-M2)") (class "Default")
      (node (ref "S02") (pin "5") (pinfunction "5_5") (pintype "passive"))
      (node (ref "SP13") (pin "2") (pinfunction "2_2") (pintype "passive"))
      (node (ref "T13") (pin "2") (pinfunction "M2_2") (pintype "bidirectional"))
      (node (ref "T13") (pin "4") (pinfunction "M2-4_4") (pintype "bidirectional"))
      (node (ref "TVS13") (pin "A") (pinfunction "A_A") (pintype "passive"))
    )
    (net (code "53") (name "Net-(T14-M2)") (class "Default")
      (node (ref "S02") (pin "6") (pinfunction "6_6") (pintype "passive"))
      (node (ref "SP14") (pin "2") (pinfunction "2_2") (pintype "passive"))
      (node (ref "T14") (pin "2") (pinfunction "M2_2") (pintype "bidirectional"))
      (node (ref "T14") (pin "4") (pinfunction "M2-4_4") (pintype "bidirectional"))
      (node (ref "TVS14") (pin "A") (pinfunction "A_A") (pintype "passive"))
    )
    (net (code "54") (name "Net-(T15-M2)") (class "Default")
      (node (ref "S02") (pin "7") (pinfunction "7_7") (pintype "passive"))
      (node (ref "SP15") (pin "2") (pinfunction "2_2") (pintype "passive"))
      (node (ref "T15") (pin "2") (pinfunction "M2_2") (pintype "bidirectional"))
      (node (ref "T15") (pin "4") (pinfunction "M2-4_4") (pintype "bidirectional"))
      (node (ref "TVS15") (pin "A") (pinfunction "A_A") (pintype "passive"))
    )
    (net (code "55") (name "Net-(T16-M2)") (class "Default")
      (node (ref "S02") (pin "8") (pinfunction "8_8") (pintype "passive"))
      (node (ref "SP16") (pin "2") (pinfunction "2_2") (pintype "passive"))
      (node (ref "T16") (pin "2") (pinfunction "M2_2") (pintype "bidirectional"))
      (node (ref "T16") (pin "4") (pinfunction "M2-4_4") (pintype "bidirectional"))
      (node (ref "TVS16") (pin "A") (pinfunction "A_A") (pintype "passive"))
    )
    (net (code "56") (name "unconnected-(JEXT1-Pad1)") (class "Default")
      (node (ref "JEXT1") (pin "1") (pinfunction "1_1") (pintype "passive"))
    )
    (net (code "57") (name "unconnected-(JEXT1-Pad2)") (class "Default")
      (node (ref "JEXT1") (pin "2") (pinfunction "2_2") (pintype "passive"))
    )
    (net (code "58") (name "unconnected-(JEXT1-Pad3)") (class "Default")
      (node (ref "JEXT1") (pin "3") (pinfunction "3_3") (pintype "passive"))
    )
    (net (code "59") (name "unconnected-(JEXT1-Pad4)") (class "Default")
      (node (ref "JEXT1") (pin "4") (pinfunction "4_4") (pintype "passive"))
    )
    (net (code "60") (name "unconnected-(JEXT2-Pad1)") (class "Default")
      (node (ref "JEXT2") (pin "1") (pinfunction "1_1") (pintype "passive"))
    )
    (net (code "61") (name "unconnected-(JEXT2-Pad2)") (class "Default")
      (node (ref "JEXT2") (pin "2") (pinfunction "2_2") (pintype "passive"))
    )
    (net (code "62") (name "unconnected-(JEXT2-Pad3)") (class "Default")
      (node (ref "JEXT2") (pin "3") (pinfunction "3_3") (pintype "passive"))
    )
    (net (code "63") (name "unconnected-(JEXT2-Pad4)") (class "Default")
      (node (ref "JEXT2") (pin "4") (pinfunction "4_4") (pintype "passive"))
    )
    (net (code "64") (name "unconnected-(PCA9555-~{INT}-Pad1)") (class "Default")
      (node (ref "PCA9555") (pin "1") (pinfunction "~{INT}_1") (pintype "bidirectional"))
    )
  )
)
